# LCDTFT_CTRL_BT818.net
KiCad netlist of a schematic drawn in Altium Designer
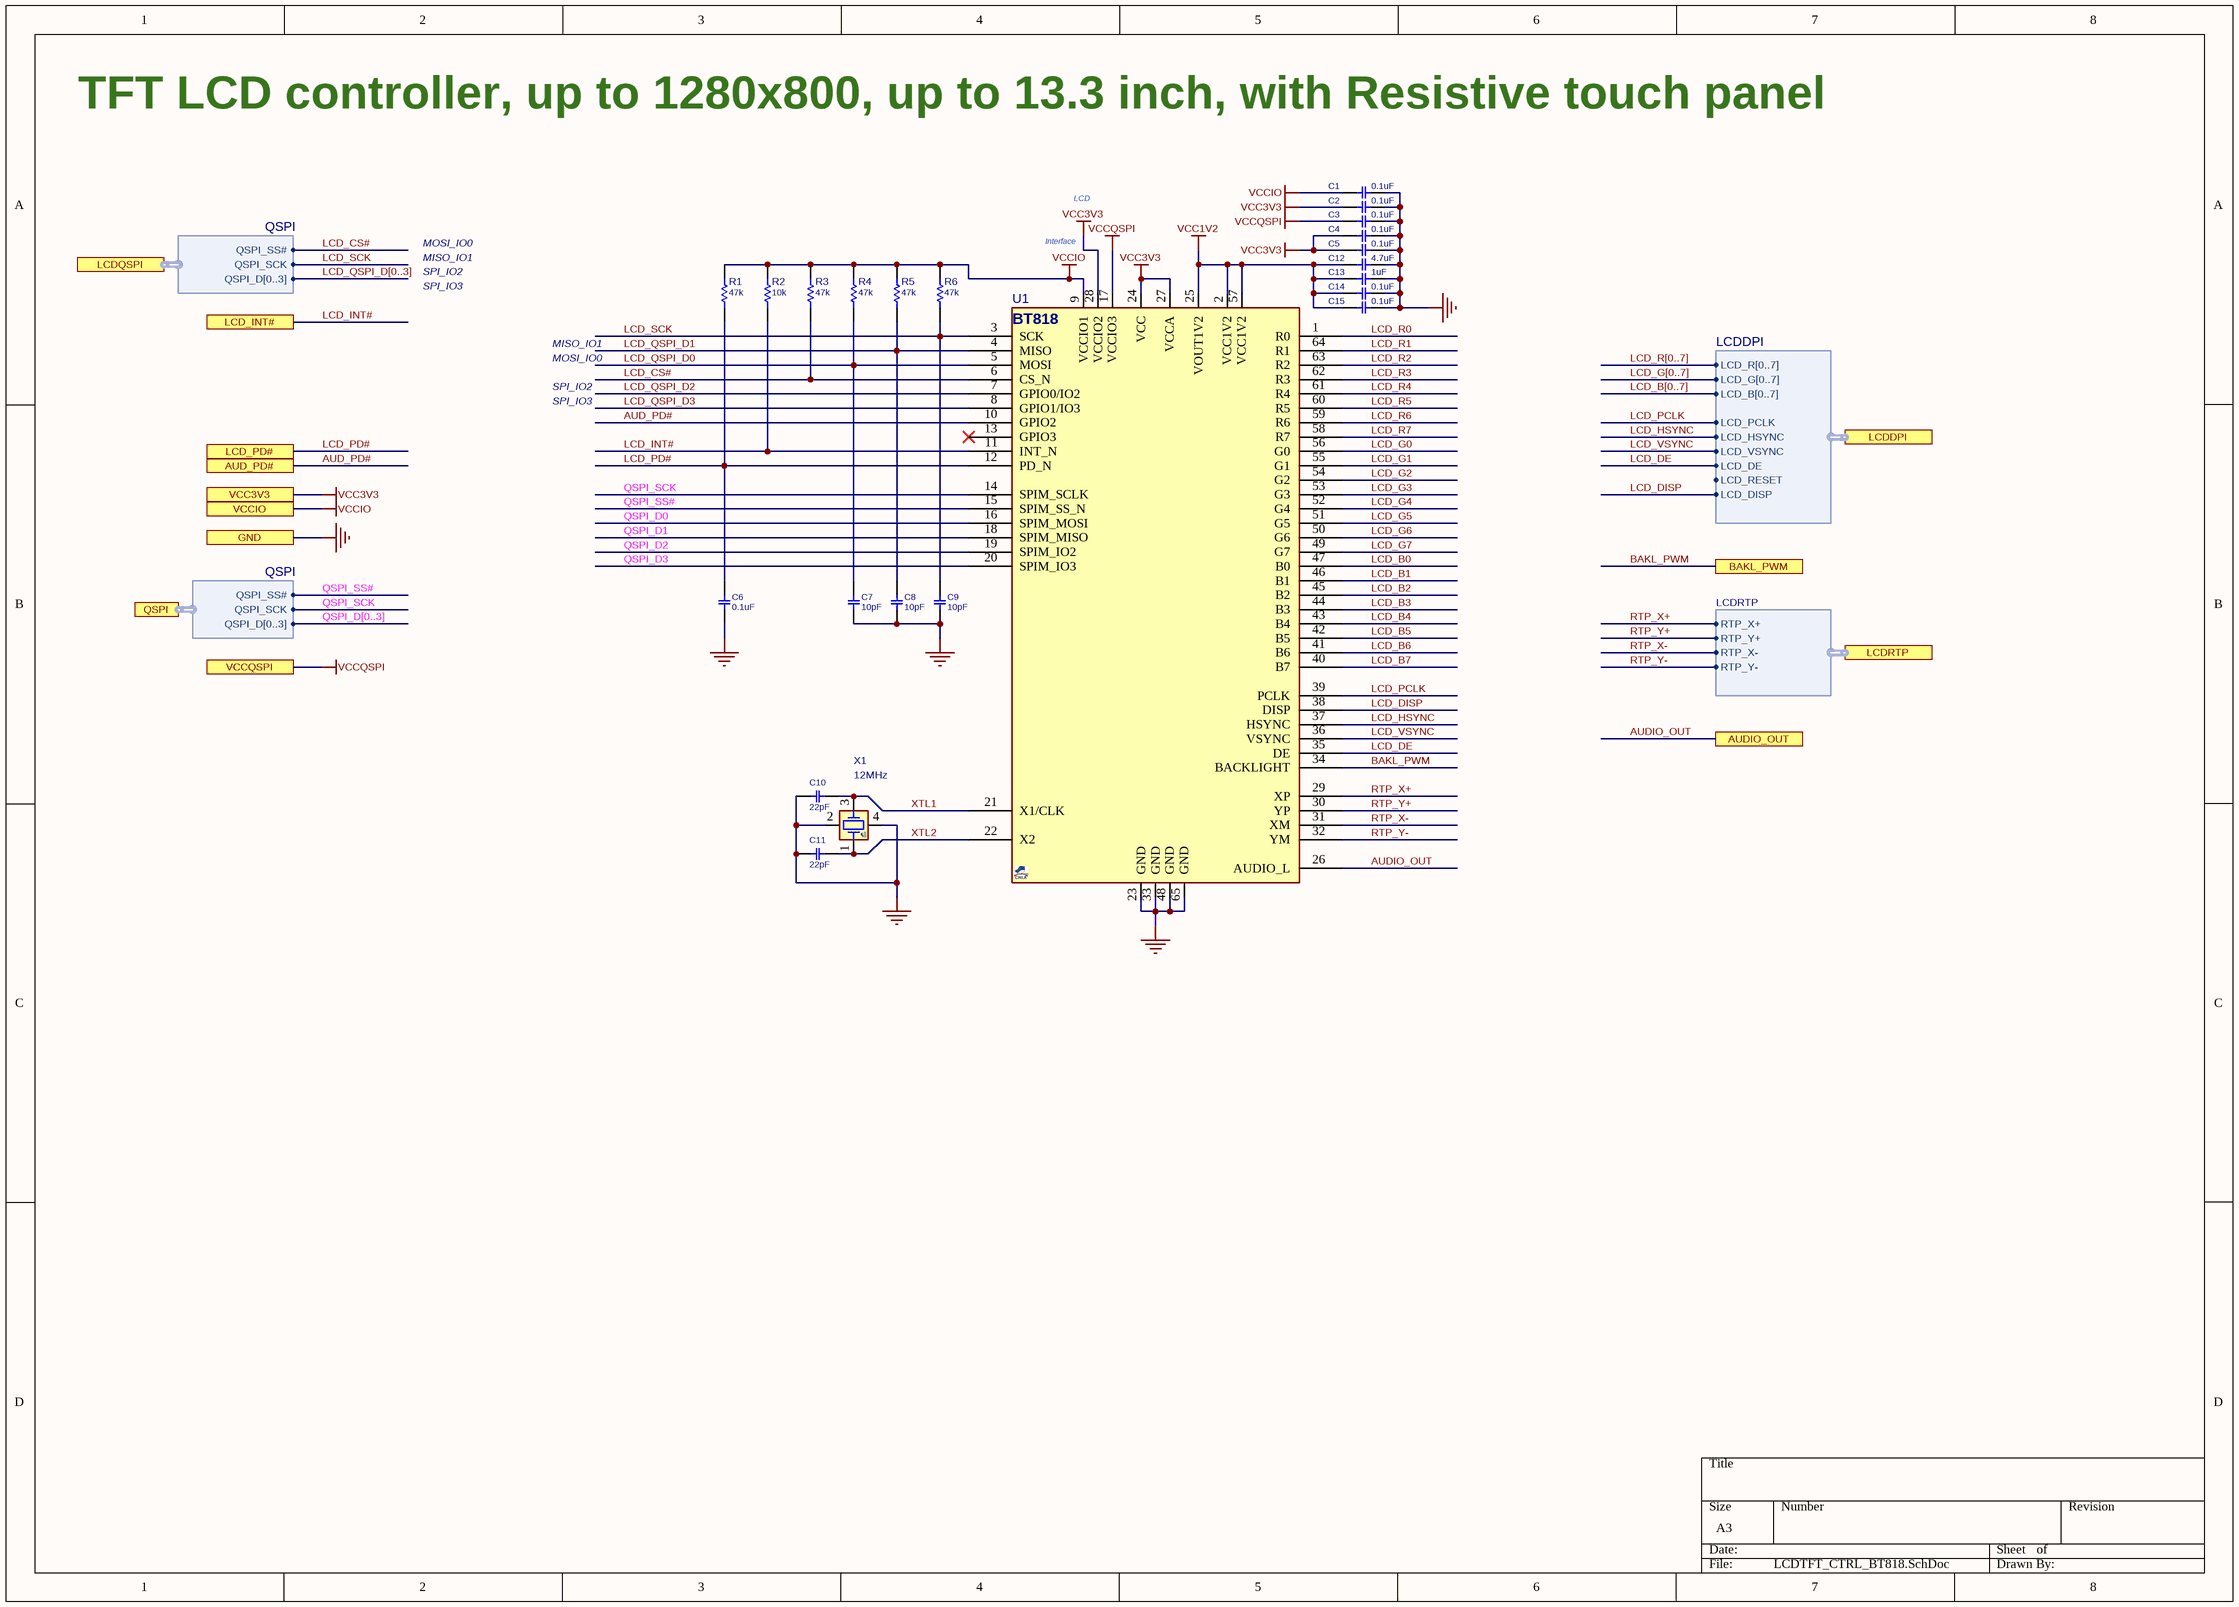
[diagram p0: LCDTFT_CTRL_BT818.SchDoc]

(export (version "E")
  (design (tool "Eeschema 10.0.6"))
  (components
    (comp (ref "C1")
      (value "0.1uF")
      (footprint "C0402")
      (description "CAP, MLCC")
      (fields (field (name "MANF_P#") "GRM155R71H104KE14D") (field (name "MANF") "Murata"))
      (libsource (lib "passive_smd") (part "CAP_SMD_MLCC"))
    )
    (comp (ref "C2")
      (value "0.1uF")
      (footprint "C0402")
      (description "CAP, MLCC")
      (fields (field (name "MANF_P#") "GRM155R71H104KE14D") (field (name "MANF") "Murata"))
      (libsource (lib "passive_smd") (part "CAP_SMD_MLCC"))
    )
    (comp (ref "C3")
      (value "0.1uF")
      (footprint "C0402")
      (description "CAP, MLCC")
      (fields (field (name "MANF_P#") "GRM155R71H104KE14D") (field (name "MANF") "Murata"))
      (libsource (lib "passive_smd") (part "CAP_SMD_MLCC"))
    )
    (comp (ref "C4")
      (value "0.1uF")
      (footprint "C0402")
      (description "CAP, MLCC")
      (fields (field (name "MANF_P#") "GRM155R71H104KE14D") (field (name "MANF") "Murata"))
      (libsource (lib "passive_smd") (part "CAP_SMD_MLCC"))
    )
    (comp (ref "C5")
      (value "0.1uF")
      (footprint "C0402")
      (description "CAP, MLCC")
      (fields (field (name "MANF_P#") "GRM155R71H104KE14D") (field (name "MANF") "Murata"))
      (libsource (lib "passive_smd") (part "CAP_SMD_MLCC"))
    )
    (comp (ref "C6")
      (value "0.1uF")
      (footprint "C0402")
      (description "CAP, MLCC")
      (fields (field (name "MANF_P#") "GRM155R71H104KE14D") (field (name "MANF") "Murata"))
      (libsource (lib "passive_smd") (part "CAP_SMD_MLCC"))
    )
    (comp (ref "C7")
      (value "10pF")
      (footprint "C0402")
      (description "CAP, MLCC")
      (libsource (lib "passive_smd") (part "CAP_SMD_MLCC"))
    )
    (comp (ref "C8")
      (value "10pF")
      (footprint "C0402")
      (description "CAP, MLCC")
      (libsource (lib "passive_smd") (part "CAP_SMD_MLCC"))
    )
    (comp (ref "C9")
      (value "10pF")
      (footprint "C0402")
      (description "CAP, MLCC")
      (libsource (lib "passive_smd") (part "CAP_SMD_MLCC"))
    )
    (comp (ref "C10")
      (value "22pF")
      (footprint "C0402")
      (description "CAP, MLCC")
      (libsource (lib "passive_smd") (part "CAP_SMD_MLCC"))
    )
    (comp (ref "C11")
      (value "22pF")
      (footprint "C0402")
      (description "CAP, MLCC")
      (libsource (lib "passive_smd") (part "CAP_SMD_MLCC"))
    )
    (comp (ref "C12")
      (value "4.7uF")
      (footprint "C0402")
      (description "CAP, MLCC")
      (libsource (lib "passive_smd") (part "CAP_SMD_MLCC"))
    )
    (comp (ref "C13")
      (value "1uF")
      (footprint "C0402")
      (description "CAP, MLCC")
      (libsource (lib "passive_smd") (part "CAP_SMD_MLCC"))
    )
    (comp (ref "C14")
      (value "0.1uF")
      (footprint "C0402")
      (description "CAP, MLCC")
      (fields (field (name "MANF_P#") "GRM155R71H104KE14D") (field (name "MANF") "Murata"))
      (libsource (lib "passive_smd") (part "CAP_SMD_MLCC"))
    )
    (comp (ref "C15")
      (value "0.1uF")
      (footprint "C0402")
      (description "CAP, MLCC")
      (fields (field (name "MANF_P#") "GRM155R71H104KE14D") (field (name "MANF") "Murata"))
      (libsource (lib "passive_smd") (part "CAP_SMD_MLCC"))
    )
    (comp (ref "R1")
      (value "47k")
      (footprint "R0402")
      (description "RESISTOR, SMD")
      (libsource (lib "passive_res_smd") (part "RES_SMD"))
    )
    (comp (ref "R2")
      (value "10k")
      (footprint "R0402")
      (description "RESISTOR, SMD")
      (libsource (lib "passive_res_smd") (part "RES_SMD"))
    )
    (comp (ref "R3")
      (value "47k")
      (footprint "R0402")
      (description "RESISTOR, SMD")
      (libsource (lib "passive_res_smd") (part "RES_SMD"))
    )
    (comp (ref "R4")
      (value "47k")
      (footprint "R0402")
      (description "RESISTOR, SMD")
      (libsource (lib "passive_res_smd") (part "RES_SMD"))
    )
    (comp (ref "R5")
      (value "47k")
      (footprint "R0402")
      (description "RESISTOR, SMD")
      (libsource (lib "passive_res_smd") (part "RES_SMD"))
    )
    (comp (ref "R6")
      (value "47k")
      (footprint "R0402")
      (description "RESISTOR, SMD")
      (libsource (lib "passive_res_smd") (part "RES_SMD"))
    )
    (comp (ref "U1")
      (value "BT818")
      (footprint "QFN50_64T")
      (description "LCD Display Controller, Embedded Video Engine, 1280X800, QFN-64")
      (fields (field (name "MANF") "FTDI/Bridgetek") (field (name "MANF_P#") "BT818Q"))
      (libsource (lib "lcdtft_controller") (part "BT818_QFN64"))
    )
    (comp (ref "X1")
      (value "12MHz")
      (footprint "XTL_4_3225")
      (description "Crystal 12MHz")
      (fields (field (name "MANF") "ECS") (field (name "MANF_P#") "ECS-120-18-33-JEM-TR"))
      (libsource (lib "crystal") (part "XTL_4_12MHz_3225"))
    )
  )
  (nets
    (net (code "4") (name "/AUDIO_OUT") (class "Default")
      (node (ref "U1") (pin "26") (pinfunction "AUDIO_L_26") (pintype "passive"))
    )
    (net (code "5") (name "/AUD_PD#") (class "Default")
      (node (ref "U1") (pin "10") (pinfunction "GPIO2_10") (pintype "passive"))
    )
    (net (code "6") (name "/BAKL_PWM") (class "Default")
      (node (ref "U1") (pin "34") (pinfunction "BACKLIGHT_34") (pintype "passive"))
    )
    (net (code "7") (name "/LCD_B0") (class "Default")
      (node (ref "U1") (pin "47") (pinfunction "B0_47") (pintype "passive"))
    )
    (net (code "8") (name "/LCD_B1") (class "Default")
      (node (ref "U1") (pin "46") (pinfunction "B1_46") (pintype "passive"))
    )
    (net (code "9") (name "/LCD_B2") (class "Default")
      (node (ref "U1") (pin "45") (pinfunction "B2_45") (pintype "passive"))
    )
    (net (code "10") (name "/LCD_B3") (class "Default")
      (node (ref "U1") (pin "44") (pinfunction "B3_44") (pintype "passive"))
    )
    (net (code "11") (name "/LCD_B4") (class "Default")
      (node (ref "U1") (pin "43") (pinfunction "B4_43") (pintype "passive"))
    )
    (net (code "12") (name "/LCD_B5") (class "Default")
      (node (ref "U1") (pin "42") (pinfunction "B5_42") (pintype "passive"))
    )
    (net (code "13") (name "/LCD_B6") (class "Default")
      (node (ref "U1") (pin "41") (pinfunction "B6_41") (pintype "passive"))
    )
    (net (code "14") (name "/LCD_B7") (class "Default")
      (node (ref "U1") (pin "40") (pinfunction "B7_40") (pintype "passive"))
    )
    (net (code "16") (name "/LCD_CS#") (class "Default")
      (node (ref "R3") (pin "2") (pinfunction "2_2") (pintype "passive"))
      (node (ref "U1") (pin "6") (pinfunction "CS_N_6") (pintype "passive"))
    )
    (net (code "17") (name "/LCD_DE") (class "Default")
      (node (ref "U1") (pin "35") (pinfunction "DE_35") (pintype "passive"))
    )
    (net (code "18") (name "/LCD_DISP") (class "Default")
      (node (ref "U1") (pin "38") (pinfunction "DISP_38") (pintype "passive"))
    )
    (net (code "19") (name "/LCD_G0") (class "Default")
      (node (ref "U1") (pin "56") (pinfunction "G0_56") (pintype "passive"))
    )
    (net (code "20") (name "/LCD_G1") (class "Default")
      (node (ref "U1") (pin "55") (pinfunction "G1_55") (pintype "passive"))
    )
    (net (code "21") (name "/LCD_G2") (class "Default")
      (node (ref "U1") (pin "54") (pinfunction "G2_54") (pintype "passive"))
    )
    (net (code "22") (name "/LCD_G3") (class "Default")
      (node (ref "U1") (pin "53") (pinfunction "G3_53") (pintype "passive"))
    )
    (net (code "23") (name "/LCD_G4") (class "Default")
      (node (ref "U1") (pin "52") (pinfunction "G4_52") (pintype "passive"))
    )
    (net (code "24") (name "/LCD_G5") (class "Default")
      (node (ref "U1") (pin "51") (pinfunction "G5_51") (pintype "passive"))
    )
    (net (code "25") (name "/LCD_G6") (class "Default")
      (node (ref "U1") (pin "50") (pinfunction "G6_50") (pintype "passive"))
    )
    (net (code "26") (name "/LCD_G7") (class "Default")
      (node (ref "U1") (pin "49") (pinfunction "G7_49") (pintype "passive"))
    )
    (net (code "28") (name "/LCD_HSYNC") (class "Default")
      (node (ref "U1") (pin "37") (pinfunction "HSYNC_37") (pintype "passive"))
    )
    (net (code "29") (name "/LCD_INT#") (class "Default")
      (node (ref "R2") (pin "2") (pinfunction "2_2") (pintype "passive"))
      (node (ref "U1") (pin "11") (pinfunction "INT_N_11") (pintype "passive"))
    )
    (net (code "30") (name "/LCD_PCLK") (class "Default")
      (node (ref "U1") (pin "39") (pinfunction "PCLK_39") (pintype "passive"))
    )
    (net (code "31") (name "/LCD_PD#") (class "Default")
      (node (ref "C6") (pin "1") (pinfunction "1_1") (pintype "passive"))
      (node (ref "R1") (pin "2") (pinfunction "2_2") (pintype "passive"))
      (node (ref "U1") (pin "12") (pinfunction "PD_N_12") (pintype "passive"))
    )
    (net (code "32") (name "/LCD_QSPI_D0") (class "Default")
      (node (ref "C7") (pin "1") (pinfunction "1_1") (pintype "passive"))
      (node (ref "R4") (pin "2") (pinfunction "2_2") (pintype "passive"))
      (node (ref "U1") (pin "5") (pinfunction "MOSI_5") (pintype "passive"))
    )
    (net (code "33") (name "/LCD_QSPI_D1") (class "Default")
      (node (ref "C8") (pin "1") (pinfunction "1_1") (pintype "passive"))
      (node (ref "R5") (pin "2") (pinfunction "2_2") (pintype "passive"))
      (node (ref "U1") (pin "4") (pinfunction "MISO_4") (pintype "passive"))
    )
    (net (code "34") (name "/LCD_QSPI_D2") (class "Default")
      (node (ref "U1") (pin "7") (pinfunction "GPIO0/IO2_7") (pintype "passive"))
    )
    (net (code "35") (name "/LCD_QSPI_D3") (class "Default")
      (node (ref "U1") (pin "8") (pinfunction "GPIO1/IO3_8") (pintype "passive"))
    )
    (net (code "37") (name "/LCD_R0") (class "Default")
      (node (ref "U1") (pin "1") (pinfunction "R0_1") (pintype "passive"))
    )
    (net (code "38") (name "/LCD_R1") (class "Default")
      (node (ref "U1") (pin "64") (pinfunction "R1_64") (pintype "passive"))
    )
    (net (code "39") (name "/LCD_R2") (class "Default")
      (node (ref "U1") (pin "63") (pinfunction "R2_63") (pintype "passive"))
    )
    (net (code "40") (name "/LCD_R3") (class "Default")
      (node (ref "U1") (pin "62") (pinfunction "R3_62") (pintype "passive"))
    )
    (net (code "41") (name "/LCD_R4") (class "Default")
      (node (ref "U1") (pin "61") (pinfunction "R4_61") (pintype "passive"))
    )
    (net (code "42") (name "/LCD_R5") (class "Default")
      (node (ref "U1") (pin "60") (pinfunction "R5_60") (pintype "passive"))
    )
    (net (code "43") (name "/LCD_R6") (class "Default")
      (node (ref "U1") (pin "59") (pinfunction "R6_59") (pintype "passive"))
    )
    (net (code "44") (name "/LCD_R7") (class "Default")
      (node (ref "U1") (pin "58") (pinfunction "R7_58") (pintype "passive"))
    )
    (net (code "46") (name "/LCD_SCK") (class "Default")
      (node (ref "C9") (pin "1") (pinfunction "1_1") (pintype "passive"))
      (node (ref "R6") (pin "2") (pinfunction "2_2") (pintype "passive"))
      (node (ref "U1") (pin "3") (pinfunction "SCK_3") (pintype "passive"))
    )
    (net (code "47") (name "/LCD_VSYNC") (class "Default")
      (node (ref "U1") (pin "36") (pinfunction "VSYNC_36") (pintype "passive"))
    )
    (net (code "48") (name "/QSPI_D0") (class "Default")
      (node (ref "U1") (pin "16") (pinfunction "SPIM_MOSI_16") (pintype "passive"))
    )
    (net (code "49") (name "/QSPI_D1") (class "Default")
      (node (ref "U1") (pin "18") (pinfunction "SPIM_MISO_18") (pintype "passive"))
    )
    (net (code "50") (name "/QSPI_D2") (class "Default")
      (node (ref "U1") (pin "19") (pinfunction "SPIM_IO2_19") (pintype "passive"))
    )
    (net (code "51") (name "/QSPI_D3") (class "Default")
      (node (ref "U1") (pin "20") (pinfunction "SPIM_IO3_20") (pintype "passive"))
    )
    (net (code "53") (name "/QSPI_SCK") (class "Default")
      (node (ref "U1") (pin "14") (pinfunction "SPIM_SCLK_14") (pintype "passive"))
    )
    (net (code "54") (name "/QSPI_SS#") (class "Default")
      (node (ref "U1") (pin "15") (pinfunction "SPIM_SS_N_15") (pintype "passive"))
    )
    (net (code "55") (name "/RTP_X+") (class "Default")
      (node (ref "U1") (pin "29") (pinfunction "XP_29") (pintype "passive"))
    )
    (net (code "56") (name "/RTP_X-") (class "Default")
      (node (ref "U1") (pin "31") (pinfunction "XM_31") (pintype "passive"))
    )
    (net (code "57") (name "/RTP_Y+") (class "Default")
      (node (ref "U1") (pin "30") (pinfunction "YP_30") (pintype "passive"))
    )
    (net (code "58") (name "/RTP_Y-") (class "Default")
      (node (ref "U1") (pin "32") (pinfunction "YM_32") (pintype "passive"))
    )
    (net (code "59") (name "/XTL1") (class "Default")
      (node (ref "C10") (pin "2") (pinfunction "2_2") (pintype "passive"))
      (node (ref "U1") (pin "21") (pinfunction "X1/CLK_21") (pintype "passive"))
      (node (ref "X1") (pin "3") (pinfunction "2_3") (pintype "passive"))
    )
    (net (code "60") (name "/XTL2") (class "Default")
      (node (ref "C11") (pin "1") (pinfunction "1_1") (pintype "passive"))
      (node (ref "U1") (pin "22") (pinfunction "X2_22") (pintype "passive"))
      (node (ref "X1") (pin "1") (pinfunction "1_1") (pintype "passive"))
    )
    (net (code "64") (name "GND") (class "Default")
      (node (ref "C1") (pin "1") (pinfunction "1_1") (pintype "passive"))
      (node (ref "C10") (pin "1") (pinfunction "1_1") (pintype "passive"))
      (node (ref "C11") (pin "2") (pinfunction "2_2") (pintype "passive"))
      (node (ref "C12") (pin "1") (pinfunction "1_1") (pintype "passive"))
      (node (ref "C13") (pin "1") (pinfunction "1_1") (pintype "passive"))
      (node (ref "C14") (pin "1") (pinfunction "1_1") (pintype "passive"))
      (node (ref "C15") (pin "1") (pinfunction "1_1") (pintype "passive"))
      (node (ref "C2") (pin "1") (pinfunction "1_1") (pintype "passive"))
      (node (ref "C3") (pin "1") (pinfunction "1_1") (pintype "passive"))
      (node (ref "C4") (pin "1") (pinfunction "1_1") (pintype "passive"))
      (node (ref "C5") (pin "1") (pinfunction "1_1") (pintype "passive"))
      (node (ref "C6") (pin "2") (pinfunction "2_2") (pintype "passive"))
      (node (ref "C7") (pin "2") (pinfunction "2_2") (pintype "passive"))
      (node (ref "C8") (pin "2") (pinfunction "2_2") (pintype "passive"))
      (node (ref "C9") (pin "2") (pinfunction "2_2") (pintype "passive"))
      (node (ref "U1") (pin "23") (pinfunction "GND_23") (pintype "passive"))
      (node (ref "U1") (pin "33") (pinfunction "GND_33") (pintype "passive"))
      (node (ref "U1") (pin "48") (pinfunction "GND_48") (pintype "passive"))
      (node (ref "U1") (pin "65") (pinfunction "GND_65") (pintype "passive"))
      (node (ref "X1") (pin "2") (pinfunction "2_2") (pintype "passive"))
      (node (ref "X1") (pin "4") (pinfunction "4_4") (pintype "passive"))
    )
    (net (code "65") (name "VCC1V2") (class "Default")
      (node (ref "C12") (pin "2") (pinfunction "2_2") (pintype "passive"))
      (node (ref "C13") (pin "2") (pinfunction "2_2") (pintype "passive"))
      (node (ref "C14") (pin "2") (pinfunction "2_2") (pintype "passive"))
      (node (ref "C15") (pin "2") (pinfunction "2_2") (pintype "passive"))
      (node (ref "U1") (pin "2") (pinfunction "VCC1V2_2") (pintype "passive"))
      (node (ref "U1") (pin "25") (pinfunction "VOUT1V2_25") (pintype "passive"))
      (node (ref "U1") (pin "57") (pinfunction "VCC1V2_57") (pintype "passive"))
    )
    (net (code "66") (name "VCC3V3") (class "Default")
      (node (ref "C2") (pin "2") (pinfunction "2_2") (pintype "passive"))
      (node (ref "C4") (pin "2") (pinfunction "2_2") (pintype "passive"))
      (node (ref "C5") (pin "2") (pinfunction "2_2") (pintype "passive"))
      (node (ref "U1") (pin "24") (pinfunction "VCC_24") (pintype "passive"))
      (node (ref "U1") (pin "27") (pinfunction "VCCA_27") (pintype "passive"))
      (node (ref "U1") (pin "28") (pinfunction "VCCIO2_28") (pintype "passive"))
    )
    (net (code "67") (name "VCCIO") (class "Default")
      (node (ref "C1") (pin "2") (pinfunction "2_2") (pintype "passive"))
      (node (ref "R1") (pin "1") (pinfunction "1_1") (pintype "passive"))
      (node (ref "R2") (pin "1") (pinfunction "1_1") (pintype "passive"))
      (node (ref "R3") (pin "1") (pinfunction "1_1") (pintype "passive"))
      (node (ref "R4") (pin "1") (pinfunction "1_1") (pintype "passive"))
      (node (ref "R5") (pin "1") (pinfunction "1_1") (pintype "passive"))
      (node (ref "R6") (pin "1") (pinfunction "1_1") (pintype "passive"))
      (node (ref "U1") (pin "9") (pinfunction "VCCIO1_9") (pintype "passive"))
    )
    (net (code "68") (name "VCCQSPI") (class "Default")
      (node (ref "C3") (pin "2") (pinfunction "2_2") (pintype "passive"))
      (node (ref "U1") (pin "17") (pinfunction "VCCIO3_17") (pintype "passive"))
    )
    (net (code "69") (name "unconnected-(U1-GPIO3-Pad13)") (class "Default")
      (node (ref "U1") (pin "13") (pinfunction "GPIO3_13") (pintype "passive+no_connect"))
    )
  )
)
